# Sheet1.net
KiCad netlist of a schematic drawn in Altium Designer
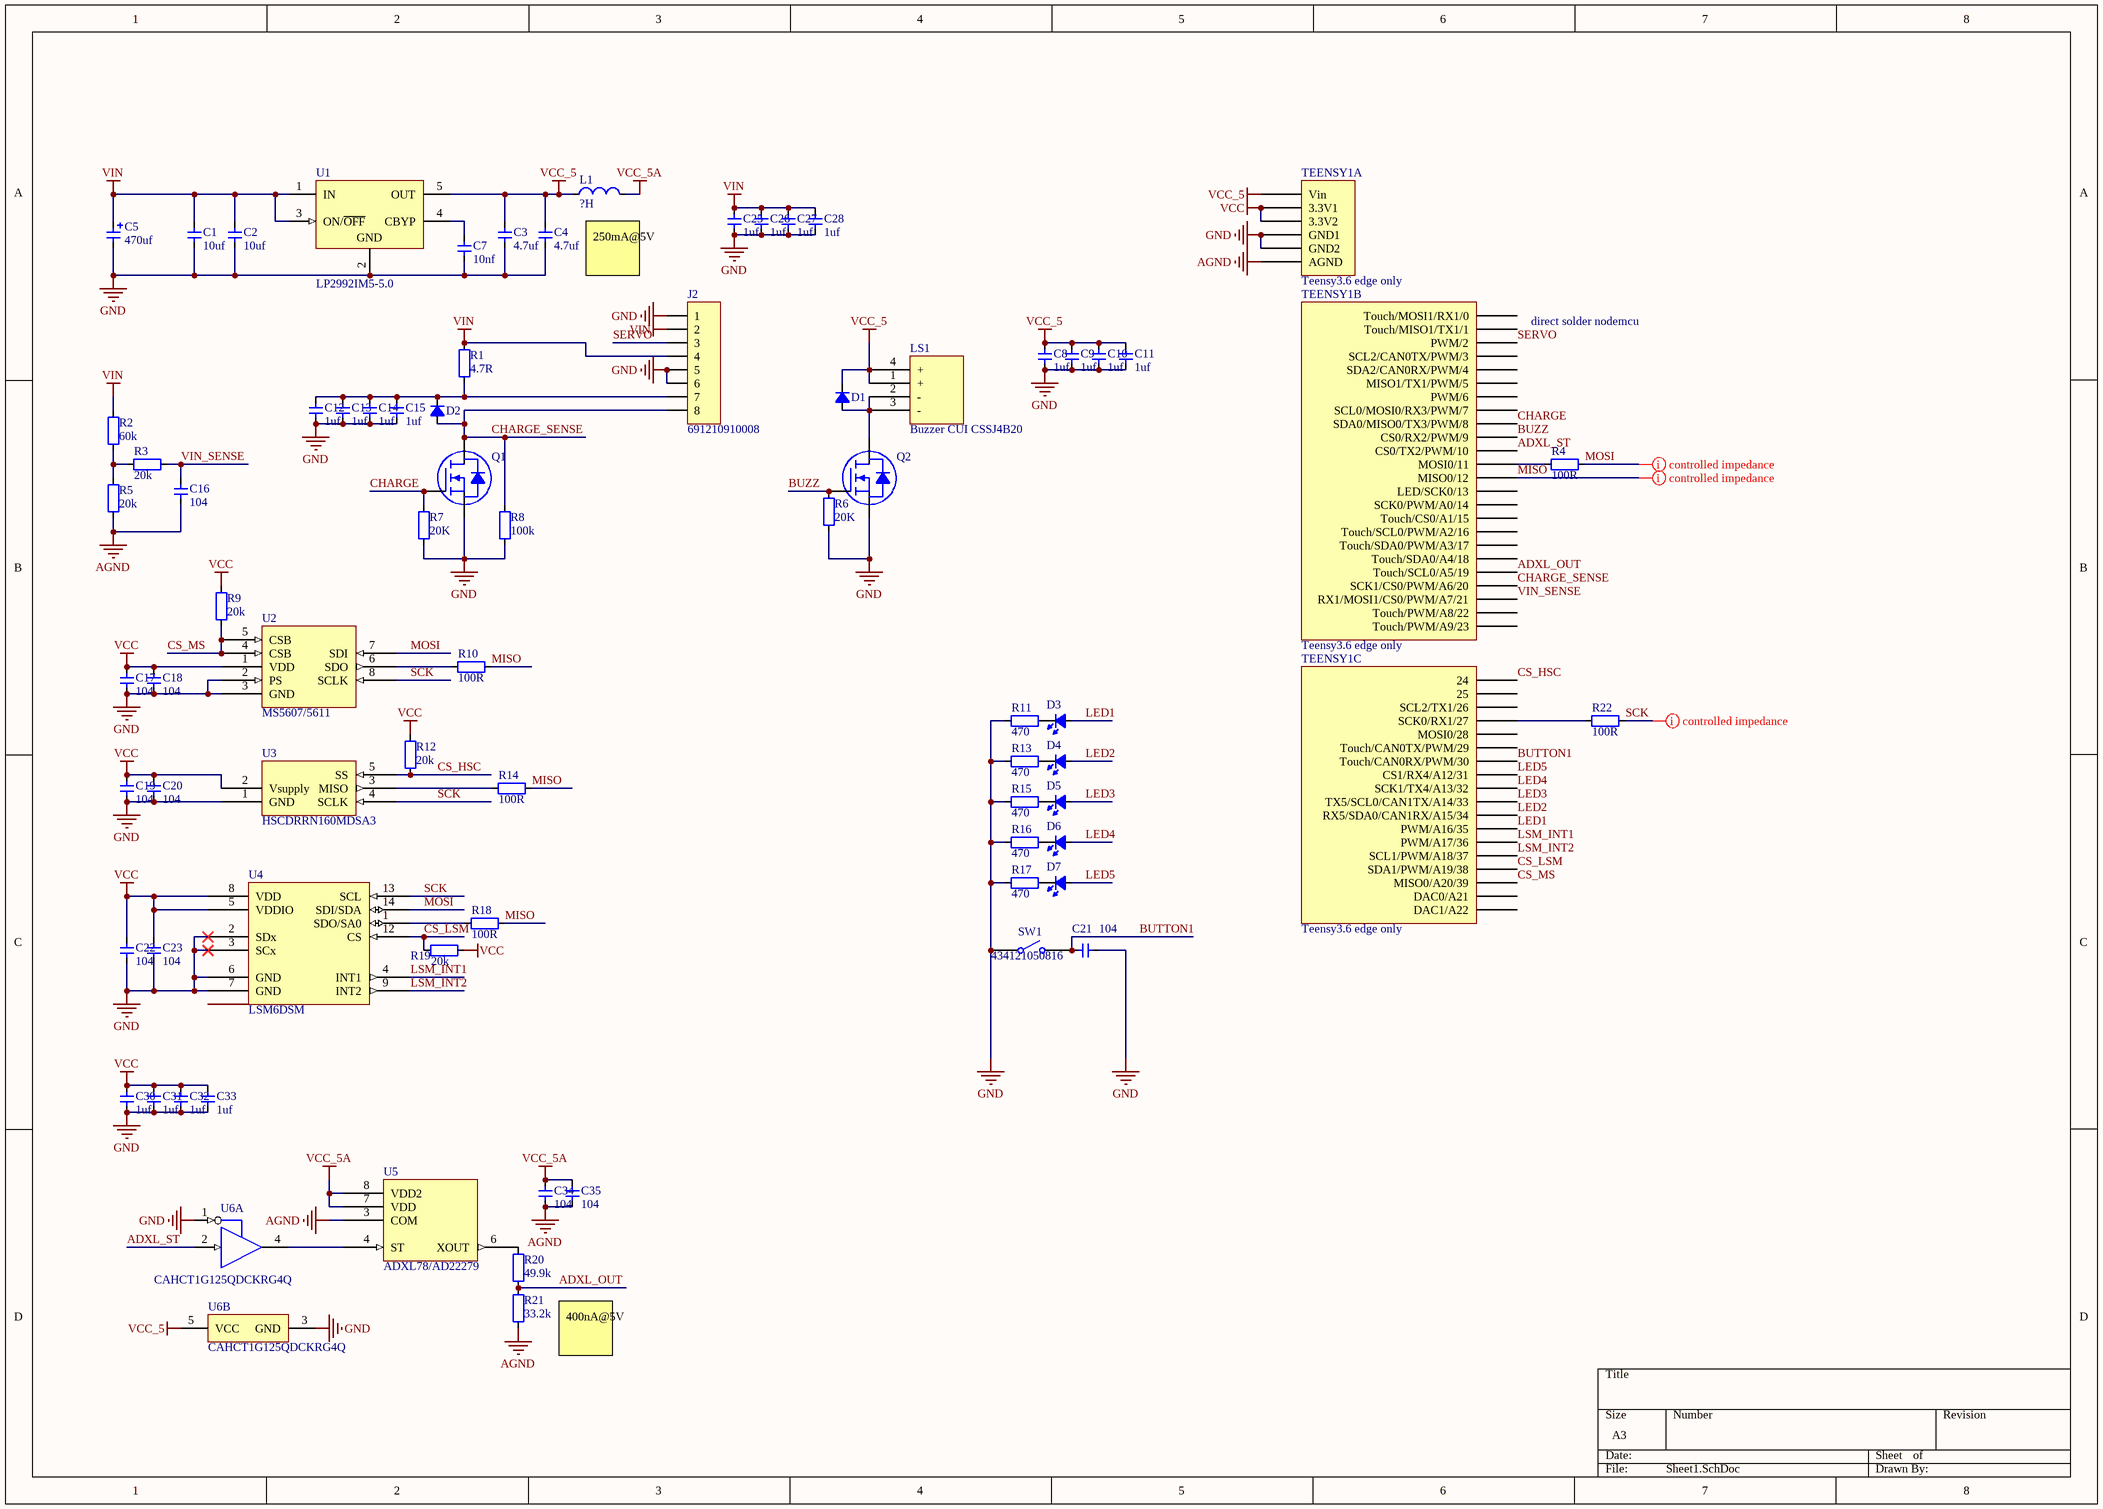
[diagram p0: Sheet1.SchDoc]

(export (version "E")
  (design (tool "Eeschema 10.0.6"))
  (components
    (comp (ref "C1")
      (value "10uf")
      (footprint "PCB_PassiveCap:CAP_0805")
      (description "Capacitor")
      (fields (field (name "Comment") "Cap_0805"))
      (libsource (lib "SCH_Passive") (part "Cap_0805"))
    )
    (comp (ref "C2")
      (value "10uf")
      (footprint "PCB_PassiveCap:CAP_0805")
      (description "Capacitor")
      (fields (field (name "Comment") "Cap_0805"))
      (libsource (lib "SCH_Passive") (part "Cap_0805"))
    )
    (comp (ref "C3")
      (value "4.7uf")
      (footprint "PCB_PassiveCap:CAP_0805")
      (description "Capacitor")
      (fields (field (name "Comment") "Cap_0805"))
      (libsource (lib "SCH_Passive") (part "Cap_0805"))
    )
    (comp (ref "C4")
      (value "4.7uf")
      (footprint "PCB_PassiveCap:CAP_0805")
      (description "Capacitor")
      (fields (field (name "Comment") "Cap_0805"))
      (libsource (lib "SCH_Passive") (part "Cap_0805"))
    )
    (comp (ref "C5")
      (value "470uf")
      (footprint "PcbLib1:OFF_BOARD_CAP_3.5mm")
      (description "Capacitor")
      (fields (field (name "Comment") "Cap_Tan_2917"))
      (libsource (lib "SCH_Passive") (part "Cap_Tan_2917"))
    )
    (comp (ref "C7")
      (value "10nf")
      (footprint "PCB_PassiveCap:CAP_0402")
      (description "Capacitor")
      (fields (field (name "Comment") "Cap_0402"))
      (libsource (lib "SCH_Passive") (part "Cap_0402"))
    )
    (comp (ref "C8")
      (value "1uf")
      (footprint "PCB_PassiveCap:CAP_0603")
      (description "Capacitor")
      (fields (field (name "Comment") "Cap_0603"))
      (libsource (lib "SCH_Passive") (part "Cap_0603"))
    )
    (comp (ref "C9")
      (value "1uf")
      (footprint "PCB_PassiveCap:CAP_0603")
      (description "Capacitor")
      (fields (field (name "Comment") "Cap_0603"))
      (libsource (lib "SCH_Passive") (part "Cap_0603"))
    )
    (comp (ref "C10")
      (value "1uf")
      (footprint "PCB_PassiveCap:CAP_0603")
      (description "Capacitor")
      (fields (field (name "Comment") "Cap_0603"))
      (libsource (lib "SCH_Passive") (part "Cap_0603"))
    )
    (comp (ref "C11")
      (value "1uf")
      (footprint "PCB_PassiveCap:CAP_0603")
      (description "Capacitor")
      (fields (field (name "Comment") "Cap_0603"))
      (libsource (lib "SCH_Passive") (part "Cap_0603"))
    )
    (comp (ref "C12")
      (value "1uf")
      (footprint "PCB_PassiveCap:CAP_0603")
      (description "Capacitor")
      (fields (field (name "Comment") "Cap_0603"))
      (libsource (lib "SCH_Passive") (part "Cap_0603"))
    )
    (comp (ref "C13")
      (value "1uf")
      (footprint "PCB_PassiveCap:CAP_0603")
      (description "Capacitor")
      (fields (field (name "Comment") "Cap_0603"))
      (libsource (lib "SCH_Passive") (part "Cap_0603"))
    )
    (comp (ref "C14")
      (value "1uf")
      (footprint "PCB_PassiveCap:CAP_0603")
      (description "Capacitor")
      (fields (field (name "Comment") "Cap_0603"))
      (libsource (lib "SCH_Passive") (part "Cap_0603"))
    )
    (comp (ref "C15")
      (value "1uf")
      (footprint "PCB_PassiveCap:CAP_0603")
      (description "Capacitor")
      (fields (field (name "Comment") "Cap_0603"))
      (libsource (lib "SCH_Passive") (part "Cap_0603"))
    )
    (comp (ref "C16")
      (value "104")
      (footprint "PCB_PassiveCap:CAP_0402")
      (description "Capacitor")
      (fields (field (name "Comment") "Cap_0402"))
      (libsource (lib "SCH_Passive") (part "Cap_0402"))
    )
    (comp (ref "C17")
      (value "104")
      (footprint "PCB_PassiveCap:CAP_0402")
      (description "Capacitor")
      (fields (field (name "Comment") "Cap_0402"))
      (libsource (lib "SCH_Passive") (part "Cap_0402"))
    )
    (comp (ref "C18")
      (value "104")
      (footprint "PCB_PassiveCap:CAP_0402")
      (description "Capacitor")
      (fields (field (name "Comment") "Cap_0402"))
      (libsource (lib "SCH_Passive") (part "Cap_0402"))
    )
    (comp (ref "C19")
      (value "104")
      (footprint "PCB_PassiveCap:CAP_0402")
      (description "Capacitor")
      (fields (field (name "Comment") "Cap_0402"))
      (libsource (lib "SCH_Passive") (part "Cap_0402"))
    )
    (comp (ref "C20")
      (value "104")
      (footprint "PCB_PassiveCap:CAP_0402")
      (description "Capacitor")
      (fields (field (name "Comment") "Cap_0402"))
      (libsource (lib "SCH_Passive") (part "Cap_0402"))
    )
    (comp (ref "C21")
      (value "104")
      (footprint "PCB_PassiveCap:CAP_0402")
      (description "Capacitor")
      (fields (field (name "Comment") "Cap_0402"))
      (libsource (lib "SCH_Passive") (part "Cap_0402"))
    )
    (comp (ref "C22")
      (value "104")
      (footprint "PCB_PassiveCap:CAP_0402")
      (description "Capacitor")
      (fields (field (name "Comment") "Cap_0402"))
      (libsource (lib "SCH_Passive") (part "Cap_0402"))
    )
    (comp (ref "C23")
      (value "104")
      (footprint "PCB_PassiveCap:CAP_0402")
      (description "Capacitor")
      (fields (field (name "Comment") "Cap_0402"))
      (libsource (lib "SCH_Passive") (part "Cap_0402"))
    )
    (comp (ref "C25")
      (value "1uf")
      (footprint "PCB_PassiveCap:CAP_0603")
      (description "Capacitor")
      (fields (field (name "Comment") "Cap_0603"))
      (libsource (lib "SCH_Passive") (part "Cap_0603"))
    )
    (comp (ref "C26")
      (value "1uf")
      (footprint "PCB_PassiveCap:CAP_0603")
      (description "Capacitor")
      (fields (field (name "Comment") "Cap_0603"))
      (libsource (lib "SCH_Passive") (part "Cap_0603"))
    )
    (comp (ref "C27")
      (value "1uf")
      (footprint "PCB_PassiveCap:CAP_0603")
      (description "Capacitor")
      (fields (field (name "Comment") "Cap_0603"))
      (libsource (lib "SCH_Passive") (part "Cap_0603"))
    )
    (comp (ref "C28")
      (value "1uf")
      (footprint "PCB_PassiveCap:CAP_0603")
      (description "Capacitor")
      (fields (field (name "Comment") "Cap_0603"))
      (libsource (lib "SCH_Passive") (part "Cap_0603"))
    )
    (comp (ref "C30")
      (value "1uf")
      (footprint "PCB_PassiveCap:CAP_0603")
      (description "Capacitor")
      (fields (field (name "Comment") "Cap_0603"))
      (libsource (lib "SCH_Passive") (part "Cap_0603"))
    )
    (comp (ref "C31")
      (value "1uf")
      (footprint "PCB_PassiveCap:CAP_0603")
      (description "Capacitor")
      (fields (field (name "Comment") "Cap_0603"))
      (libsource (lib "SCH_Passive") (part "Cap_0603"))
    )
    (comp (ref "C32")
      (value "1uf")
      (footprint "PCB_PassiveCap:CAP_0603")
      (description "Capacitor")
      (fields (field (name "Comment") "Cap_0603"))
      (libsource (lib "SCH_Passive") (part "Cap_0603"))
    )
    (comp (ref "C33")
      (value "1uf")
      (footprint "PCB_PassiveCap:CAP_0603")
      (description "Capacitor")
      (fields (field (name "Comment") "Cap_0603"))
      (libsource (lib "SCH_Passive") (part "Cap_0603"))
    )
    (comp (ref "C34")
      (value "104")
      (footprint "PCB_PassiveCap:CAP_0402")
      (description "Capacitor")
      (fields (field (name "Comment") "Cap_0402"))
      (libsource (lib "SCH_Passive") (part "Cap_0402"))
    )
    (comp (ref "C35")
      (value "104")
      (footprint "PCB_PassiveCap:CAP_0402")
      (description "Capacitor")
      (fields (field (name "Comment") "Cap_0402"))
      (libsource (lib "SCH_Passive") (part "Cap_0402"))
    )
    (comp (ref "D1")
      (value "Diode_SOD523")
      (footprint "SOT95P240X120-3N")
      (description "Diode")
      (libsource (lib "SCH_Active") (part "Diode_SOD523"))
    )
    (comp (ref "D2")
      (value "Diode_SOD523")
      (footprint "SOT95P240X120-3N")
      (description "Diode")
      (libsource (lib "SCH_Active") (part "Diode_SOD523"))
    )
    (comp (ref "D3")
      (value "LED_0402")
      (footprint "PCB_ActiveLED:LED_0402_RED")
      (description "LED")
      (libsource (lib "SCH_Active") (part "LED_0402"))
    )
    (comp (ref "D4")
      (value "LED_0402")
      (footprint "PCB_ActiveLED:LED_0402_RED")
      (description "LED")
      (libsource (lib "SCH_Active") (part "LED_0402"))
    )
    (comp (ref "D5")
      (value "LED_0402")
      (footprint "PCB_ActiveLED:LED_0402_RED")
      (description "LED")
      (libsource (lib "SCH_Active") (part "LED_0402"))
    )
    (comp (ref "D6")
      (value "LED_0402")
      (footprint "PCB_ActiveLED:LED_0402_RED")
      (description "LED")
      (libsource (lib "SCH_Active") (part "LED_0402"))
    )
    (comp (ref "D7")
      (value "LED_0402")
      (footprint "PCB_ActiveLED:LED_0402_RED")
      (description "LED")
      (libsource (lib "SCH_Active") (part "LED_0402"))
    )
    (comp (ref "J2")
      (value "691210910008")
      (footprint "691210910008")
      (description "WR-TBL Terminal Blocks Serie 2109 - 2.54 mm with Rising Cage Clamp")
      (fields
        (field (name "MANUFACTURER") "Würth Elektronik eiSos GmbH")
        (field (name "CREATED DATE") "8 Novenber 2013")
        (field (name "CREATED BY") "Karrer Zheng")
      )
      (libsource (lib "ALTIUM-TBL_2_54_2109_HORIZONTAL_ENTRY_69121091000X-rev15c") (part "691210910008"))
    )
    (comp (ref "L1")
      (value "?H")
      (footprint "PCB_PassiveInd:IND_0603")
      (description "Inductor")
      (fields (field (name "Comment") "Ind_0603"))
      (libsource (lib "SCH_Passive") (part "Ind_0603"))
    )
    (comp (ref "LS1")
      (value "Buzzer CUI CSSJ4B20")
      (footprint "CUI Buzzer 8.5")
      (libsource (lib "Schlib1") (part "CSS-J4B20"))
    )
    (comp (ref "Q1")
      (value "INFINEON MOSFET N-CH SOT-23-3")
      (footprint "INFINEON SOT-23-3")
      (libsource (lib "N-CH FETs") (part "INFINEON MOSFET N-CH SOT-23-3"))
    )
    (comp (ref "Q2")
      (value "INFINEON MOSFET N-CH SOT-23-3")
      (footprint "INFINEON SOT-23-3")
      (libsource (lib "N-CH FETs") (part "INFINEON MOSFET N-CH SOT-23-3"))
    )
    (comp (ref "R1")
      (value "4.7R")
      (footprint "PCB_PassiveRes:RES_0805")
      (description "Resistor")
      (fields (field (name "Comment") "Res_0805"))
      (libsource (lib "SCH_Passive") (part "Res_0805"))
    )
    (comp (ref "R2")
      (value "60k")
      (footprint "PCB_PassiveRes:RES_0402")
      (description "Resistor")
      (fields (field (name "Comment") "Res_0402"))
      (libsource (lib "SCH_Passive") (part "Res_0402"))
    )
    (comp (ref "R3")
      (value "20k")
      (footprint "PCB_PassiveRes:RES_0402")
      (description "Resistor")
      (fields (field (name "Comment") "Res_0402"))
      (libsource (lib "") (part "Res_0402_1"))
    )
    (comp (ref "R4")
      (value "100R")
      (footprint "PCB_PassiveRes:RES_0402")
      (description "Resistor")
      (fields (field (name "Comment") "Res_0402"))
      (libsource (lib "SCH_Passive") (part "Res_0402"))
    )
    (comp (ref "R5")
      (value "20k")
      (footprint "PCB_PassiveRes:RES_0402")
      (description "Resistor")
      (fields (field (name "Comment") "Res_0402"))
      (libsource (lib "SCH_Passive") (part "Res_0402"))
    )
    (comp (ref "R6")
      (value "20K")
      (footprint "PCB_PassiveRes:RES_0402")
      (description "Resistor")
      (fields (field (name "Comment") "Res_0402"))
      (libsource (lib "") (part "Res_0402_2"))
    )
    (comp (ref "R7")
      (value "20K")
      (footprint "PCB_PassiveRes:RES_0402")
      (description "Resistor")
      (fields (field (name "Comment") "Res_0402"))
      (libsource (lib "") (part "Res_0402_2"))
    )
    (comp (ref "R8")
      (value "100k")
      (footprint "PCB_PassiveRes:RES_0402")
      (description "Resistor")
      (fields (field (name "Comment") "Res_0402"))
      (libsource (lib "") (part "Res_0402_2"))
    )
    (comp (ref "R9")
      (value "20k")
      (footprint "PCB_PassiveRes:RES_0402")
      (description "Resistor")
      (fields (field (name "Comment") "Res_0402"))
      (libsource (lib "") (part "Res_0402_2"))
    )
    (comp (ref "R10")
      (value "100R")
      (footprint "PCB_PassiveRes:RES_0402")
      (description "Resistor")
      (fields (field (name "Comment") "Res_0402"))
      (libsource (lib "SCH_Passive") (part "Res_0402"))
    )
    (comp (ref "R11")
      (value "470")
      (footprint "PCB_PassiveRes:RES_0402")
      (description "Resistor")
      (fields (field (name "Comment") "Res_0402"))
      (libsource (lib "SCH_Passive") (part "Res_0402"))
    )
    (comp (ref "R12")
      (value "20k")
      (footprint "PCB_PassiveRes:RES_0402")
      (description "Resistor")
      (fields (field (name "Comment") "Res_0402"))
      (libsource (lib "") (part "Res_0402_2"))
    )
    (comp (ref "R13")
      (value "470")
      (footprint "PCB_PassiveRes:RES_0402")
      (description "Resistor")
      (fields (field (name "Comment") "Res_0402"))
      (libsource (lib "SCH_Passive") (part "Res_0402"))
    )
    (comp (ref "R14")
      (value "100R")
      (footprint "PCB_PassiveRes:RES_0402")
      (description "Resistor")
      (fields (field (name "Comment") "Res_0402"))
      (libsource (lib "SCH_Passive") (part "Res_0402"))
    )
    (comp (ref "R15")
      (value "470")
      (footprint "PCB_PassiveRes:RES_0402")
      (description "Resistor")
      (fields (field (name "Comment") "Res_0402"))
      (libsource (lib "SCH_Passive") (part "Res_0402"))
    )
    (comp (ref "R16")
      (value "470")
      (footprint "PCB_PassiveRes:RES_0402")
      (description "Resistor")
      (fields (field (name "Comment") "Res_0402"))
      (libsource (lib "SCH_Passive") (part "Res_0402"))
    )
    (comp (ref "R17")
      (value "470")
      (footprint "PCB_PassiveRes:RES_0402")
      (description "Resistor")
      (fields (field (name "Comment") "Res_0402"))
      (libsource (lib "SCH_Passive") (part "Res_0402"))
    )
    (comp (ref "R18")
      (value "100R")
      (footprint "PCB_PassiveRes:RES_0402")
      (description "Resistor")
      (fields (field (name "Comment") "Res_0402"))
      (libsource (lib "SCH_Passive") (part "Res_0402"))
    )
    (comp (ref "R19")
      (value "20k")
      (footprint "PCB_PassiveRes:RES_0402")
      (description "Resistor")
      (fields (field (name "Comment") "Res_0402"))
      (libsource (lib "SCH_Passive") (part "Res_0402"))
    )
    (comp (ref "R20")
      (value "49.9k")
      (footprint "PCB_PassiveRes:RES_0402")
      (description "Resistor")
      (fields (field (name "Comment") "Res_0402"))
      (libsource (lib "") (part "Res_0402_1"))
    )
    (comp (ref "R21")
      (value "33.2k")
      (footprint "PCB_PassiveRes:RES_0402")
      (description "Resistor")
      (fields (field (name "Comment") "Res_0402"))
      (libsource (lib "") (part "Res_0402_2"))
    )
    (comp (ref "R22")
      (value "100R")
      (footprint "PCB_PassiveRes:RES_0402")
      (description "Resistor")
      (fields (field (name "Comment") "Res_0402"))
      (libsource (lib "SCH_Passive") (part "Res_0402"))
    )
    (comp (ref "SW1")
      (value "434121050816")
      (footprint "434121050816")
      (description "WS-TASV SMD Tact Switch 6.0X3.5 mm")
      (fields (field (name "MANUFACTURER") "Wuerth Elektronik"))
      (libsource (lib "Altium Content Vault") (part "WE-TACT-SW-2"))
    )
    (comp (ref "TEENSY1")
      (value "Teensy3.6 edge only")
      (footprint "Teensy3.6-edgeonly")
      (libsource (lib "teensy3.6") (part "Teensy3.6 edge only"))
    )
    (comp (ref "U1")
      (value "LP2992IM5-5.0")
      (footprint "DBV0005A_N")
      (description "Micropower 250 mA Low-Noise Ultra Low-Dropout Regulator, 5-pin SOT-23")
      (fields (field (name "MANUFACTURER") "Texas Instruments"))
      (libsource (lib "Altium Content Vault") (part "PM-REG-LP2985-SOT5"))
    )
    (comp (ref "U2") (value "MS5607/5611") (footprint "MS5611") (libsource (lib "Schlib1") (part "MS5611")))
    (comp (ref "U3")
      (value "HSCDRRN160MDSA3")
      (footprint "honeywell-hsc-DIP8")
      (libsource (lib "Schlib1") (part "honeywell-hsc-spi"))
    )
    (comp (ref "U4")
      (value "LSM6DSM")
      (footprint "LGA14L_DOT_INDICATOR")
      (libsource (lib "Schlib1") (part "LSM6DS3"))
    )
    (comp (ref "U5")
      (value "ADXL78/AD22279")
      (footprint "ADI-E-8-1_V")
      (libsource (lib "Schlib1") (part "ADXL78"))
    )
    (comp (ref "U6")
      (value "CAHCT1G125QDCKRG4Q")
      (footprint "DCK0005A_M")
      (description "Automotive Catalog Single Bus Buffer Gate With 3-State Output, DCK0005A, LARGE T&R")
      (fields
        (field (name "GENERIC PART NUMBER") "SN74AHCT1G125-Q1")
        (field (name "MANUFACTURER") "Texas Instruments")
      )
      (libsource (lib "Altium Content Vault") (part "TI-SN74AXXXX1X125-5"))
    )
  )
  (nets
    (net (code "1") (name "/ADXL_OUT") (class "Default")
      (node (ref "R20") (pin "2") (pinfunction "2_2") (pintype "passive"))
      (node (ref "R21") (pin "2") (pinfunction "2_2") (pintype "passive"))
      (node (ref "TEENSY1") (pin "19") (pinfunction "Touch/SCL0/A5/19_19") (pintype "passive"))
    )
    (net (code "2") (name "/ADXL_ST") (class "Default")
      (node (ref "TEENSY1") (pin "10") (pinfunction "CS0/TX2/PWM/10_10") (pintype "passive"))
      (node (ref "U6") (pin "2") (pinfunction "A_2") (pintype "input"))
    )
    (net (code "3") (name "/BUTTON1") (class "Default")
      (node (ref "C21") (pin "1") (pinfunction "1_1") (pintype "passive"))
      (node (ref "SW1") (pin "2") (pinfunction "2_2") (pintype "passive"))
      (node (ref "TEENSY1") (pin "30") (pinfunction "Touch/CAN0RX/PWM/30_30") (pintype "passive"))
    )
    (net (code "4") (name "/BUZZ") (class "Default")
      (node (ref "Q2") (pin "1") (pinfunction "G_1") (pintype "passive"))
      (node (ref "R6") (pin "2") (pinfunction "2_2") (pintype "passive"))
      (node (ref "TEENSY1") (pin "9") (pinfunction "CS0/RX2/PWM/9_9") (pintype "passive"))
    )
    (net (code "5") (name "/CHARGE") (class "Default")
      (node (ref "Q1") (pin "1") (pinfunction "G_1") (pintype "passive"))
      (node (ref "R7") (pin "2") (pinfunction "2_2") (pintype "passive"))
      (node (ref "TEENSY1") (pin "8") (pinfunction "SDA0/MISO0/TX3/PWM/8_8") (pintype "passive"))
    )
    (net (code "6") (name "/CHARGE_SENSE") (class "Default")
      (node (ref "D2") (pin "1") (pinfunction "A_1") (pintype "passive"))
      (node (ref "J2") (pin "8") (pinfunction "8_8") (pintype "passive"))
      (node (ref "Q1") (pin "2") (pinfunction "D_2") (pintype "passive"))
      (node (ref "R8") (pin "2") (pinfunction "2_2") (pintype "passive"))
      (node (ref "TEENSY1") (pin "20") (pinfunction "SCK1/CS0/PWM/A6/20_20") (pintype "passive"))
    )
    (net (code "7") (name "/CS_HSC") (class "Default")
      (node (ref "R12") (pin "1") (pinfunction "1_1") (pintype "passive"))
      (node (ref "TEENSY1") (pin "24") (pinfunction "24_24") (pintype "passive"))
      (node (ref "U3") (pin "5") (pinfunction "SS_5") (pintype "input"))
    )
    (net (code "8") (name "/CS_LSM") (class "Default")
      (node (ref "R19") (pin "1") (pinfunction "1_1") (pintype "passive"))
      (node (ref "TEENSY1") (pin "38") (pinfunction "SDA1/PWM/A19/38_38") (pintype "passive"))
      (node (ref "U4") (pin "12") (pinfunction "CS_12") (pintype "input"))
    )
    (net (code "9") (name "/CS_MS") (class "Default")
      (node (ref "R9") (pin "1") (pinfunction "1_1") (pintype "passive"))
      (node (ref "TEENSY1") (pin "39") (pinfunction "MISO0/A20/39_39") (pintype "passive"))
      (node (ref "U2") (pin "4") (pinfunction "CSB_4") (pintype "input"))
      (node (ref "U2") (pin "5") (pinfunction "CSB_5") (pintype "input"))
    )
    (net (code "10") (name "/LED1") (class "Default")
      (node (ref "D3") (pin "1") (pinfunction "A_1") (pintype "passive"))
      (node (ref "TEENSY1") (pin "35") (pinfunction "PWM/A16/35_35") (pintype "passive"))
    )
    (net (code "11") (name "/LED2") (class "Default")
      (node (ref "D4") (pin "1") (pinfunction "A_1") (pintype "passive"))
      (node (ref "TEENSY1") (pin "34") (pinfunction "RX5/SDA0/CAN1RX/A15/34_34") (pintype "passive"))
    )
    (net (code "12") (name "/LED3") (class "Default")
      (node (ref "D5") (pin "1") (pinfunction "A_1") (pintype "passive"))
      (node (ref "TEENSY1") (pin "33") (pinfunction "TX5/SCL0/CAN1TX/A14/33_33") (pintype "passive"))
    )
    (net (code "13") (name "/LED4") (class "Default")
      (node (ref "D6") (pin "1") (pinfunction "A_1") (pintype "passive"))
      (node (ref "TEENSY1") (pin "32") (pinfunction "SCK1/TX4/A13/32_32") (pintype "passive"))
    )
    (net (code "14") (name "/LED5") (class "Default")
      (node (ref "D7") (pin "1") (pinfunction "A_1") (pintype "passive"))
      (node (ref "TEENSY1") (pin "31") (pinfunction "CS1/RX4/A12/31_31") (pintype "passive"))
    )
    (net (code "15") (name "/LSM_INT1") (class "Default")
      (node (ref "TEENSY1") (pin "36") (pinfunction "PWM/A17/36_36") (pintype "passive"))
      (node (ref "U4") (pin "4") (pinfunction "INT1_4") (pintype "output"))
    )
    (net (code "16") (name "/LSM_INT2") (class "Default")
      (node (ref "TEENSY1") (pin "37") (pinfunction "SCL1/PWM/A18/37_37") (pintype "passive"))
      (node (ref "U4") (pin "9") (pinfunction "INT2_9") (pintype "output"))
    )
    (net (code "17") (name "/MISO") (class "Default")
      (node (ref "R10") (pin "2") (pinfunction "2_2") (pintype "passive"))
      (node (ref "R14") (pin "2") (pinfunction "2_2") (pintype "passive"))
      (node (ref "R18") (pin "2") (pinfunction "2_2") (pintype "passive"))
      (node (ref "TEENSY1") (pin "12") (pinfunction "MISO0/12_12") (pintype "passive"))
    )
    (net (code "18") (name "/MOSI") (class "Default")
      (node (ref "R4") (pin "2") (pinfunction "2_2") (pintype "passive"))
      (node (ref "U2") (pin "7") (pinfunction "SDI_7") (pintype "input"))
      (node (ref "U4") (pin "14") (pinfunction "SDI/SDA_14") (pintype "bidirectional"))
    )
    (net (code "19") (name "/SCK") (class "Default")
      (node (ref "R22") (pin "2") (pinfunction "2_2") (pintype "passive"))
      (node (ref "U2") (pin "8") (pinfunction "SCLK_8") (pintype "input"))
      (node (ref "U3") (pin "4") (pinfunction "SCLK_4") (pintype "input"))
      (node (ref "U4") (pin "13") (pinfunction "SCL_13") (pintype "input"))
    )
    (net (code "20") (name "/SERVO") (class "Default")
      (node (ref "J2") (pin "3") (pinfunction "3_3") (pintype "passive"))
      (node (ref "TEENSY1") (pin "2") (pinfunction "PWM/2_2") (pintype "passive"))
    )
    (net (code "21") (name "/VIN_SENSE") (class "Default")
      (node (ref "C16") (pin "2") (pinfunction "2_2") (pintype "passive"))
      (node (ref "R3") (pin "1") (pinfunction "1_1") (pintype "passive"))
      (node (ref "TEENSY1") (pin "21") (pinfunction "RX1/MOSI1/CS0/PWM/A7/21_21") (pintype "passive"))
    )
    (net (code "22") (name "AGND") (class "Default")
      (node (ref "C16") (pin "1") (pinfunction "1_1") (pintype "passive"))
      (node (ref "C34") (pin "1") (pinfunction "1_1") (pintype "passive"))
      (node (ref "C35") (pin "1") (pinfunction "1_1") (pintype "passive"))
      (node (ref "R21") (pin "1") (pinfunction "1_1") (pintype "passive"))
      (node (ref "R5") (pin "1") (pinfunction "1_1") (pintype "passive"))
      (node (ref "TEENSY1") (pin "AGND") (pinfunction "AGND_AGND") (pintype "power_in"))
      (node (ref "U5") (pin "3") (pinfunction "COM_3") (pintype "power_in"))
    )
    (net (code "23") (name "GND") (class "Default")
      (node (ref "C1") (pin "1") (pinfunction "1_1") (pintype "passive"))
      (node (ref "C10") (pin "1") (pinfunction "1_1") (pintype "passive"))
      (node (ref "C11") (pin "1") (pinfunction "1_1") (pintype "passive"))
      (node (ref "C12") (pin "1") (pinfunction "1_1") (pintype "passive"))
      (node (ref "C13") (pin "1") (pinfunction "1_1") (pintype "passive"))
      (node (ref "C14") (pin "1") (pinfunction "1_1") (pintype "passive"))
      (node (ref "C15") (pin "1") (pinfunction "1_1") (pintype "passive"))
      (node (ref "C17") (pin "1") (pinfunction "1_1") (pintype "passive"))
      (node (ref "C18") (pin "1") (pinfunction "1_1") (pintype "passive"))
      (node (ref "C19") (pin "1") (pinfunction "1_1") (pintype "passive"))
      (node (ref "C2") (pin "1") (pinfunction "1_1") (pintype "passive"))
      (node (ref "C20") (pin "1") (pinfunction "1_1") (pintype "passive"))
      (node (ref "C21") (pin "2") (pinfunction "2_2") (pintype "passive"))
      (node (ref "C22") (pin "1") (pinfunction "1_1") (pintype "passive"))
      (node (ref "C23") (pin "1") (pinfunction "1_1") (pintype "passive"))
      (node (ref "C25") (pin "1") (pinfunction "1_1") (pintype "passive"))
      (node (ref "C26") (pin "1") (pinfunction "1_1") (pintype "passive"))
      (node (ref "C27") (pin "1") (pinfunction "1_1") (pintype "passive"))
      (node (ref "C28") (pin "1") (pinfunction "1_1") (pintype "passive"))
      (node (ref "C3") (pin "1") (pinfunction "1_1") (pintype "passive"))
      (node (ref "C30") (pin "1") (pinfunction "1_1") (pintype "passive"))
      (node (ref "C31") (pin "1") (pinfunction "1_1") (pintype "passive"))
      (node (ref "C32") (pin "1") (pinfunction "1_1") (pintype "passive"))
      (node (ref "C33") (pin "1") (pinfunction "1_1") (pintype "passive"))
      (node (ref "C4") (pin "1") (pinfunction "1_1") (pintype "passive"))
      (node (ref "C5") (pin "2") (pinfunction "2_2") (pintype "passive"))
      (node (ref "C7") (pin "1") (pinfunction "1_1") (pintype "passive"))
      (node (ref "C8") (pin "1") (pinfunction "1_1") (pintype "passive"))
      (node (ref "C9") (pin "1") (pinfunction "1_1") (pintype "passive"))
      (node (ref "J2") (pin "1") (pinfunction "1_1") (pintype "passive"))
      (node (ref "J2") (pin "5") (pinfunction "5_5") (pintype "passive"))
      (node (ref "J2") (pin "6") (pinfunction "6_6") (pintype "passive"))
      (node (ref "Q1") (pin "3") (pinfunction "S_3") (pintype "passive"))
      (node (ref "Q2") (pin "3") (pinfunction "S_3") (pintype "passive"))
      (node (ref "R11") (pin "1") (pinfunction "1_1") (pintype "passive"))
      (node (ref "R13") (pin "1") (pinfunction "1_1") (pintype "passive"))
      (node (ref "R15") (pin "1") (pinfunction "1_1") (pintype "passive"))
      (node (ref "R16") (pin "1") (pinfunction "1_1") (pintype "passive"))
      (node (ref "R17") (pin "1") (pinfunction "1_1") (pintype "passive"))
      (node (ref "R6") (pin "1") (pinfunction "1_1") (pintype "passive"))
      (node (ref "R7") (pin "1") (pinfunction "1_1") (pintype "passive"))
      (node (ref "R8") (pin "1") (pinfunction "1_1") (pintype "passive"))
      (node (ref "SW1") (pin "1") (pinfunction "1_1") (pintype "passive"))
      (node (ref "TEENSY1") (pin "GND1") (pinfunction "GND1_GND1") (pintype "power_in"))
      (node (ref "TEENSY1") (pin "GND2") (pinfunction "GND2_GND2") (pintype "power_in"))
      (node (ref "U1") (pin "2") (pinfunction "GND_2") (pintype "power_in"))
      (node (ref "U2") (pin "2") (pinfunction "PS_2") (pintype "input"))
      (node (ref "U2") (pin "3") (pinfunction "GND_3") (pintype "power_in"))
      (node (ref "U3") (pin "1") (pinfunction "GND_1") (pintype "power_in"))
      (node (ref "U4") (pin "2") (pinfunction "SDx_2") (pintype "open_collector"))
      (node (ref "U4") (pin "3") (pinfunction "SCx_3") (pintype "open_collector"))
      (node (ref "U4") (pin "6") (pinfunction "GND_6") (pintype "power_in"))
      (node (ref "U4") (pin "7") (pinfunction "GND_7") (pintype "power_in"))
      (node (ref "U6") (pin "1") (pinfunction "~{OE}_1") (pintype "input"))
      (node (ref "U6") (pin "3") (pinfunction "GND_3") (pintype "power_in"))
    )
    (net (code "24") (name "Net-(D1-A)") (class "Default")
      (node (ref "D1") (pin "1") (pinfunction "A_1") (pintype "passive"))
      (node (ref "LS1") (pin "2") (pinfunction "-_2") (pintype "passive"))
      (node (ref "LS1") (pin "3") (pinfunction "-_3") (pintype "passive"))
      (node (ref "Q2") (pin "2") (pinfunction "D_2") (pintype "passive"))
    )
    (net (code "25") (name "Net-(D2-K)") (class "Default")
      (node (ref "C12") (pin "2") (pinfunction "2_2") (pintype "passive"))
      (node (ref "C13") (pin "2") (pinfunction "2_2") (pintype "passive"))
      (node (ref "C14") (pin "2") (pinfunction "2_2") (pintype "passive"))
      (node (ref "C15") (pin "2") (pinfunction "2_2") (pintype "passive"))
      (node (ref "D2") (pin "2") (pinfunction "K_2") (pintype "passive"))
      (node (ref "J2") (pin "7") (pinfunction "7_7") (pintype "passive"))
      (node (ref "R1") (pin "1") (pinfunction "1_1") (pintype "passive"))
    )
    (net (code "26") (name "Net-(D3-K)") (class "Default")
      (node (ref "D3") (pin "2") (pinfunction "K_2") (pintype "passive"))
      (node (ref "R11") (pin "2") (pinfunction "2_2") (pintype "passive"))
    )
    (net (code "27") (name "Net-(D4-K)") (class "Default")
      (node (ref "D4") (pin "2") (pinfunction "K_2") (pintype "passive"))
      (node (ref "R13") (pin "2") (pinfunction "2_2") (pintype "passive"))
    )
    (net (code "28") (name "Net-(D5-K)") (class "Default")
      (node (ref "D5") (pin "2") (pinfunction "K_2") (pintype "passive"))
      (node (ref "R15") (pin "2") (pinfunction "2_2") (pintype "passive"))
    )
    (net (code "29") (name "Net-(D6-K)") (class "Default")
      (node (ref "D6") (pin "2") (pinfunction "K_2") (pintype "passive"))
      (node (ref "R16") (pin "2") (pinfunction "2_2") (pintype "passive"))
    )
    (net (code "30") (name "Net-(D7-K)") (class "Default")
      (node (ref "D7") (pin "2") (pinfunction "K_2") (pintype "passive"))
      (node (ref "R17") (pin "2") (pinfunction "2_2") (pintype "passive"))
    )
    (net (code "31") (name "Net-(R2-Pad1)") (class "Default")
      (node (ref "R2") (pin "1") (pinfunction "1_1") (pintype "passive"))
      (node (ref "R3") (pin "2") (pinfunction "2_2") (pintype "passive"))
      (node (ref "R5") (pin "2") (pinfunction "2_2") (pintype "passive"))
    )
    (net (code "32") (name "Net-(TEENSY1B-MOSI0{slash}11)") (class "Default")
      (node (ref "R4") (pin "1") (pinfunction "1_1") (pintype "passive"))
      (node (ref "TEENSY1") (pin "11") (pinfunction "MOSI0/11_11") (pintype "passive"))
    )
    (net (code "33") (name "Net-(TEENSY1C-SCK0{slash}RX1{slash}27)") (class "Default")
      (node (ref "R22") (pin "1") (pinfunction "1_1") (pintype "passive"))
      (node (ref "TEENSY1") (pin "27") (pinfunction "SCK0/RX1/27_27") (pintype "passive"))
    )
    (net (code "34") (name "Net-(U1-CBYP)") (class "Default")
      (node (ref "C7") (pin "2") (pinfunction "2_2") (pintype "passive"))
      (node (ref "U1") (pin "4") (pinfunction "CBYP_4") (pintype "passive"))
    )
    (net (code "35") (name "Net-(U2-SDO)") (class "Default")
      (node (ref "R10") (pin "1") (pinfunction "1_1") (pintype "passive"))
      (node (ref "U2") (pin "6") (pinfunction "SDO_6") (pintype "output"))
    )
    (net (code "36") (name "Net-(U3-MISO)") (class "Default")
      (node (ref "R14") (pin "1") (pinfunction "1_1") (pintype "passive"))
      (node (ref "U3") (pin "3") (pinfunction "MISO_3") (pintype "output"))
    )
    (net (code "37") (name "Net-(U4-SDO{slash}SA0)") (class "Default")
      (node (ref "R18") (pin "1") (pinfunction "1_1") (pintype "passive"))
      (node (ref "U4") (pin "1") (pinfunction "SDO/SA0_1") (pintype "bidirectional"))
    )
    (net (code "38") (name "Net-(U5-ST)") (class "Default")
      (node (ref "U5") (pin "4") (pinfunction "ST_4") (pintype "input"))
      (node (ref "U6") (pin "4") (pinfunction "Y_4") (pintype "tri_state"))
    )
    (net (code "39") (name "Net-(U5-XOUT)") (class "Default")
      (node (ref "R20") (pin "1") (pinfunction "1_1") (pintype "passive"))
      (node (ref "U5") (pin "6") (pinfunction "XOUT_6") (pintype "output"))
    )
    (net (code "40") (name "VCC") (class "Default")
      (node (ref "C17") (pin "2") (pinfunction "2_2") (pintype "passive"))
      (node (ref "C18") (pin "2") (pinfunction "2_2") (pintype "passive"))
      (node (ref "C19") (pin "2") (pinfunction "2_2") (pintype "passive"))
      (node (ref "C20") (pin "2") (pinfunction "2_2") (pintype "passive"))
      (node (ref "C22") (pin "2") (pinfunction "2_2") (pintype "passive"))
      (node (ref "C23") (pin "2") (pinfunction "2_2") (pintype "passive"))
      (node (ref "C30") (pin "2") (pinfunction "2_2") (pintype "passive"))
      (node (ref "C31") (pin "2") (pinfunction "2_2") (pintype "passive"))
      (node (ref "C32") (pin "2") (pinfunction "2_2") (pintype "passive"))
      (node (ref "C33") (pin "2") (pinfunction "2_2") (pintype "passive"))
      (node (ref "R12") (pin "2") (pinfunction "2_2") (pintype "passive"))
      (node (ref "R19") (pin "2") (pinfunction "2_2") (pintype "passive"))
      (node (ref "R9") (pin "2") (pinfunction "2_2") (pintype "passive"))
      (node (ref "TEENSY1") (pin "3.3V1") (pinfunction "3.3V1_3.3V1") (pintype "power_in"))
      (node (ref "TEENSY1") (pin "3.3V2") (pinfunction "3.3V2_3.3V2") (pintype "power_in"))
      (node (ref "U2") (pin "1") (pinfunction "VDD_1") (pintype "power_in"))
      (node (ref "U3") (pin "2") (pinfunction "Vsupply_2") (pintype "power_in"))
      (node (ref "U4") (pin "5") (pinfunction "VDDIO_5") (pintype "power_in"))
      (node (ref "U4") (pin "8") (pinfunction "VDD_8") (pintype "power_in"))
    )
    (net (code "41") (name "VCC_5") (class "Default")
      (node (ref "C10") (pin "2") (pinfunction "2_2") (pintype "passive"))
      (node (ref "C11") (pin "2") (pinfunction "2_2") (pintype "passive"))
      (node (ref "C3") (pin "2") (pinfunction "2_2") (pintype "passive"))
      (node (ref "C4") (pin "2") (pinfunction "2_2") (pintype "passive"))
      (node (ref "C8") (pin "2") (pinfunction "2_2") (pintype "passive"))
      (node (ref "C9") (pin "2") (pinfunction "2_2") (pintype "passive"))
      (node (ref "D1") (pin "2") (pinfunction "K_2") (pintype "passive"))
      (node (ref "L1") (pin "1") (pinfunction "1_1") (pintype "passive"))
      (node (ref "LS1") (pin "1") (pinfunction "+_1") (pintype "passive"))
      (node (ref "LS1") (pin "4") (pinfunction "+_4") (pintype "passive"))
      (node (ref "TEENSY1") (pin "VIN") (pinfunction "Vin_VIN") (pintype "power_in"))
      (node (ref "U1") (pin "5") (pinfunction "OUT_5") (pintype "power_in"))
      (node (ref "U6") (pin "5") (pinfunction "VCC_5") (pintype "power_in"))
    )
    (net (code "42") (name "VCC_5A") (class "Default")
      (node (ref "C34") (pin "2") (pinfunction "2_2") (pintype "passive"))
      (node (ref "C35") (pin "2") (pinfunction "2_2") (pintype "passive"))
      (node (ref "L1") (pin "2") (pinfunction "2_2") (pintype "passive"))
      (node (ref "U5") (pin "7") (pinfunction "VDD_7") (pintype "power_in"))
      (node (ref "U5") (pin "8") (pinfunction "VDD2_8") (pintype "power_in"))
    )
    (net (code "43") (name "VIN") (class "Default")
      (node (ref "C1") (pin "2") (pinfunction "2_2") (pintype "passive"))
      (node (ref "C2") (pin "2") (pinfunction "2_2") (pintype "passive"))
      (node (ref "C25") (pin "2") (pinfunction "2_2") (pintype "passive"))
      (node (ref "C26") (pin "2") (pinfunction "2_2") (pintype "passive"))
      (node (ref "C27") (pin "2") (pinfunction "2_2") (pintype "passive"))
      (node (ref "C28") (pin "2") (pinfunction "2_2") (pintype "passive"))
      (node (ref "C5") (pin "1") (pinfunction "1_1") (pintype "passive"))
      (node (ref "J2") (pin "2") (pinfunction "2_2") (pintype "passive"))
      (node (ref "J2") (pin "4") (pinfunction "4_4") (pintype "passive"))
      (node (ref "R1") (pin "2") (pinfunction "2_2") (pintype "passive"))
      (node (ref "R2") (pin "2") (pinfunction "2_2") (pintype "passive"))
      (node (ref "U1") (pin "1") (pinfunction "IN_1") (pintype "power_in"))
      (node (ref "U1") (pin "3") (pinfunction "ON/~{OFF}_3") (pintype "input"))
    )
    (net (code "44") (name "unconnected-(TEENSY1-Pad25)") (class "Default")
      (node (ref "TEENSY1") (pin "25") (pinfunction "25_25") (pintype "passive"))
    )
    (net (code "45") (name "unconnected-(TEENSY1B-LED{slash}SCK0{slash}13-Pad13)") (class "Default")
      (node (ref "TEENSY1") (pin "13") (pinfunction "LED/SCK0/13_13") (pintype "passive"))
    )
    (net (code "46") (name "unconnected-(TEENSY1B-MISO1{slash}TX1{slash}PWM{slash}5-Pad5)") (class "Default")
      (node (ref "TEENSY1") (pin "5") (pinfunction "MISO1/TX1/PWM/5_5") (pintype "passive"))
    )
    (net (code "47") (name "unconnected-(TEENSY1B-PWM{slash}6-Pad6)") (class "Default")
      (node (ref "TEENSY1") (pin "6") (pinfunction "PWM/6_6") (pintype "passive"))
    )
    (net (code "48") (name "unconnected-(TEENSY1B-SCK0{slash}PWM{slash}A0{slash}14-Pad14)") (class "Default")
      (node (ref "TEENSY1") (pin "14") (pinfunction "SCK0/PWM/A0/14_14") (pintype "passive"))
    )
    (net (code "49") (name "unconnected-(TEENSY1B-SCL0{slash}MOSI0{slash}RX3{slash}PWM{slash}7-Pad7)") (class "Default")
      (node (ref "TEENSY1") (pin "7") (pinfunction "SCL0/MOSI0/RX3/PWM/7_7") (pintype "passive"))
    )
    (net (code "50") (name "unconnected-(TEENSY1B-SCL2{slash}CAN0TX{slash}PWM{slash}3-Pad3)") (class "Default")
      (node (ref "TEENSY1") (pin "3") (pinfunction "SCL2/CAN0TX/PWM/3_3") (pintype "passive"))
    )
    (net (code "51") (name "unconnected-(TEENSY1B-SDA2{slash}CAN0RX{slash}PWM{slash}4-Pad4)") (class "Default")
      (node (ref "TEENSY1") (pin "4") (pinfunction "SDA2/CAN0RX/PWM/4_4") (pintype "passive"))
    )
    (net (code "52") (name "unconnected-(TEENSY1B-Touch{slash}CS0{slash}A1{slash}15-Pad15)") (class "Default")
      (node (ref "TEENSY1") (pin "15") (pinfunction "Touch/CS0/A1/15_15") (pintype "passive"))
    )
    (net (code "53") (name "unconnected-(TEENSY1B-Touch{slash}MISO1{slash}TX1{slash}1-Pad1)") (class "Default")
      (node (ref "TEENSY1") (pin "1") (pinfunction "Touch/MISO1/TX1/1_1") (pintype "passive"))
    )
    (net (code "54") (name "unconnected-(TEENSY1B-Touch{slash}MOSI1{slash}RX1{slash}0-Pad0)") (class "Default")
      (node (ref "TEENSY1") (pin "0") (pinfunction "Touch/MOSI1/RX1/0_0") (pintype "passive"))
    )
    (net (code "55") (name "unconnected-(TEENSY1B-Touch{slash}PWM{slash}A8{slash}22-Pad22)") (class "Default")
      (node (ref "TEENSY1") (pin "22") (pinfunction "Touch/PWM/A8/22_22") (pintype "passive"))
    )
    (net (code "56") (name "unconnected-(TEENSY1B-Touch{slash}PWM{slash}A9{slash}23-Pad23)") (class "Default")
      (node (ref "TEENSY1") (pin "23") (pinfunction "Touch/PWM/A9/23_23") (pintype "passive"))
    )
    (net (code "57") (name "unconnected-(TEENSY1B-Touch{slash}SCL0{slash}PWM{slash}A2{slash}16-Pad16)") (class "Default")
      (node (ref "TEENSY1") (pin "16") (pinfunction "Touch/SCL0/PWM/A2/16_16") (pintype "passive"))
    )
    (net (code "58") (name "unconnected-(TEENSY1B-Touch{slash}SDA0{slash}A4{slash}18-Pad18)") (class "Default")
      (node (ref "TEENSY1") (pin "18") (pinfunction "Touch/SDA0/A4/18_18") (pintype "passive"))
    )
    (net (code "59") (name "unconnected-(TEENSY1B-Touch{slash}SDA0{slash}PWM{slash}A3{slash}17-Pad17)") (class "Default")
      (node (ref "TEENSY1") (pin "17") (pinfunction "Touch/SDA0/PWM/A3/17_17") (pintype "passive"))
    )
    (net (code "60") (name "unconnected-(TEENSY1C-DAC0{slash}A21-PadA21)") (class "Default")
      (node (ref "TEENSY1") (pin "A21") (pinfunction "DAC0/A21_A21") (pintype "passive"))
    )
    (net (code "61") (name "unconnected-(TEENSY1C-DAC1{slash}A22-PadA22)") (class "Default")
      (node (ref "TEENSY1") (pin "A22") (pinfunction "DAC1/A22_A22") (pintype "passive"))
    )
    (net (code "62") (name "unconnected-(TEENSY1C-MOSI0{slash}28-Pad28)") (class "Default")
      (node (ref "TEENSY1") (pin "28") (pinfunction "MOSI0/28_28") (pintype "passive"))
    )
    (net (code "63") (name "unconnected-(TEENSY1C-SCL2{slash}TX1{slash}26-Pad26)") (class "Default")
      (node (ref "TEENSY1") (pin "26") (pinfunction "SCL2/TX1/26_26") (pintype "passive"))
    )
    (net (code "64") (name "unconnected-(TEENSY1C-Touch{slash}CAN0TX{slash}PWM{slash}29-Pad29)") (class "Default")
      (node (ref "TEENSY1") (pin "29") (pinfunction "Touch/CAN0TX/PWM/29_29") (pintype "passive"))
    )
  )
)
